# neon-lamb-spec-calibration.net
KiCad netlist of a schematic drawn in EAGLE
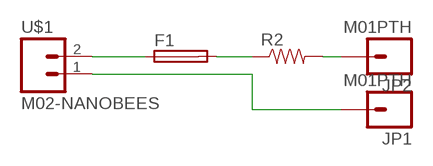
[diagram p0: schematic, sheet 1]

(export (version "E")
  (design (tool "Eeschema 10.0.6"))
  (components
    (comp (ref "F1")
      (value "GSH15")
      (footprint "eagle-import:GSH15")
      (fields (field (name "MPN") "64900001039"))
      (libsource (lib "eagle-import") (part "GSH15"))
    )
    (comp (ref "JP1")
      (value "M01PTH")
      (footprint "eagle-import:1X01")
      (libsource (lib "eagle-import") (part "M01PTH"))
    )
    (comp (ref "JP2")
      (value "M01PTH")
      (footprint "eagle-import:1X01")
      (libsource (lib "eagle-import") (part "M01PTH"))
    )
    (comp (ref "R2")
      (value "RESISTORPTH-1W")
      (footprint "eagle-import:AXIAL-0.6")
      (libsource (lib "eagle-import") (part "RESISTORPTH-1W"))
    )
    (comp (ref "U$1")
      (value "M02-NANOBEES")
      (footprint "eagle-import:M02-NANOBEES")
      (libsource (lib "eagle-import") (part "M02-NANOBEES"))
    )
  )
  (nets
    (net (code "1") (name "Net-(F1-Pad1)") (class "Default")
      (node (ref "F1") (pin "1") (pinfunction "1_1") (pintype "passive"))
      (node (ref "U$1") (pin "2") (pinfunction "2_2") (pintype "passive"))
    )
    (net (code "2") (name "Net-(JP1-Pad1)") (class "Default")
      (node (ref "JP1") (pin "1") (pinfunction "1_1") (pintype "passive"))
      (node (ref "U$1") (pin "1") (pinfunction "1_1") (pintype "passive"))
    )
    (net (code "3") (name "Net-(R2-1)") (class "Default")
      (node (ref "F1") (pin "2") (pinfunction "2_2") (pintype "passive"))
      (node (ref "R2") (pin "P$1") (pinfunction "1_P$1") (pintype "passive"))
    )
    (net (code "4") (name "Net-(R2-2)") (class "Default")
      (node (ref "JP2") (pin "1") (pinfunction "1_1") (pintype "passive"))
      (node (ref "R2") (pin "P$2") (pinfunction "2_P$2") (pintype "passive"))
    )
  )
)
